# Low_Power_Brushed_Motor_Controller.net
KiCad netlist of a schematic drawn in Altium Designer
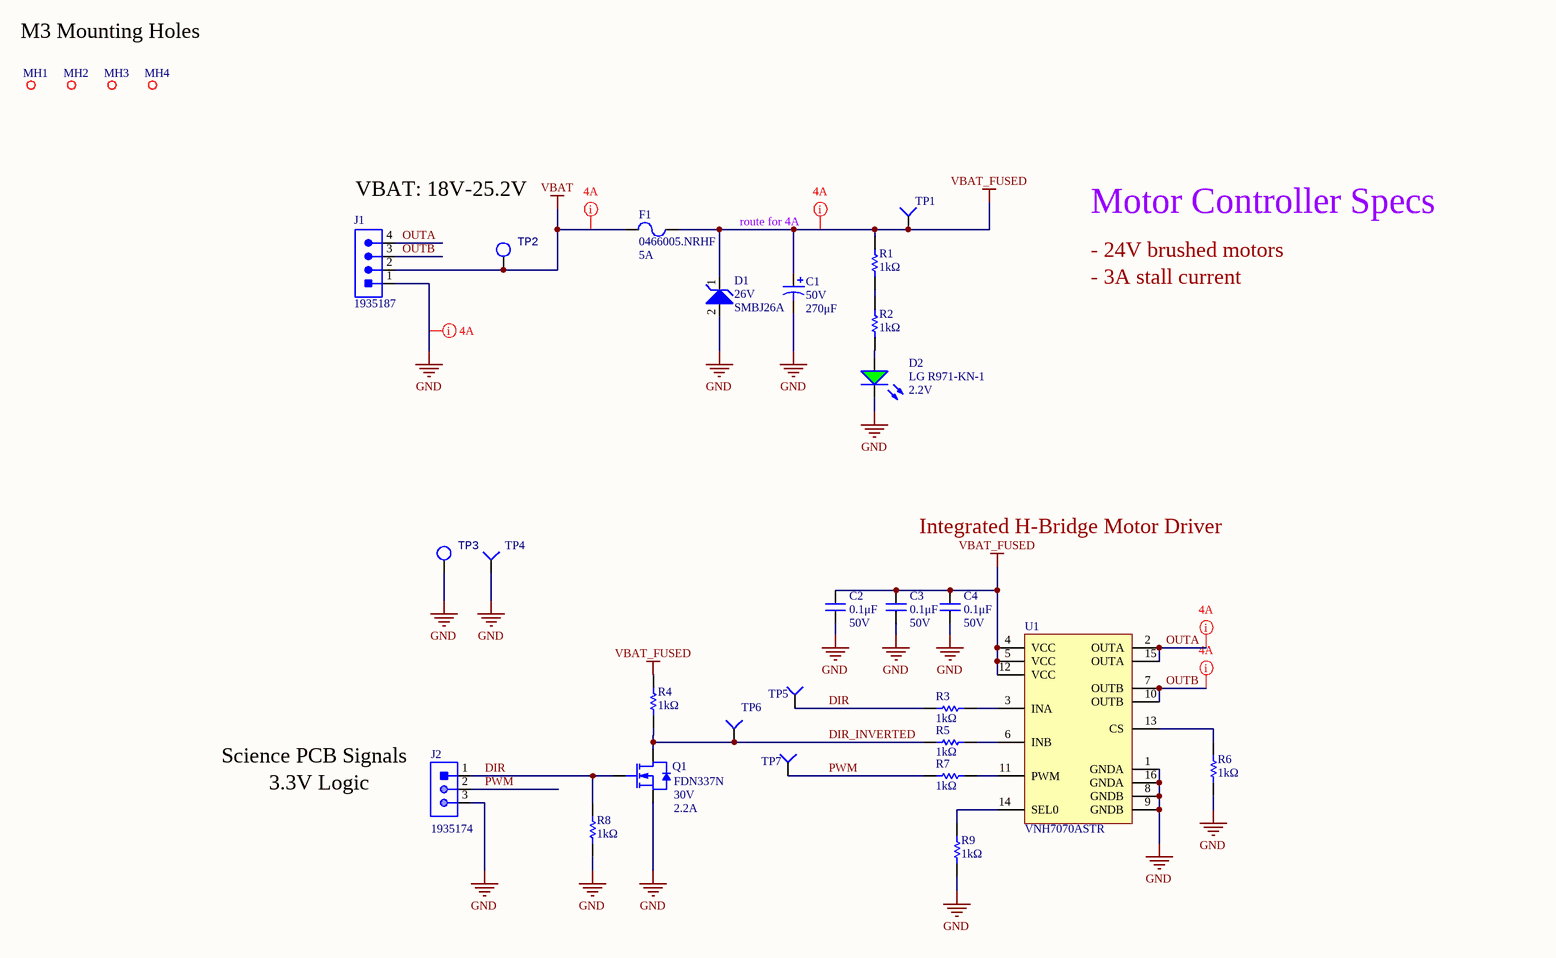
[diagram p0: Low Power Brushed Motor Controller.SchDoc]

(export (version "E")
  (design (tool "Eeschema 10.0.6"))
  (components
    (comp (ref "C1")
      (value "270μF")
      (footprint "RADIAL_PANASONIC_G")
      (description "CAP ALUM 270uF 50VDC 20% SMD")
      (fields (field (name "VOLTAGE RATING") "50V") (field (name "Comment") "CAP_270uF_50V_ALUM"))
      (libsource (lib "UWRT_Schematic_Library_2020") (part "CAP_270uF_50V_ALUM"))
    )
    (comp (ref "C2")
      (value "0.1μF")
      (footprint "CAP0603")
      (description "CAP CER 0.1UF 50V X7R 0603")
      (fields (field (name "VOLTAGE RATING") "50V") (field (name "Comment") "CAP_0.1uF_50V_0603"))
      (libsource (lib "UWRT_Schematic_Library_2020") (part "CAP_0.1uF_50V_0603"))
    )
    (comp (ref "C3")
      (value "0.1μF")
      (footprint "CAP0603")
      (description "CAP CER 0.1UF 50V X7R 0603")
      (fields (field (name "VOLTAGE RATING") "50V") (field (name "Comment") "CAP_0.1uF_50V_0603"))
      (libsource (lib "UWRT_Schematic_Library_2020") (part "CAP_0.1uF_50V_0603"))
    )
    (comp (ref "C4")
      (value "0.1μF")
      (footprint "CAP0603")
      (description "CAP CER 0.1UF 50V X7R 0603")
      (fields (field (name "VOLTAGE RATING") "50V") (field (name "Comment") "CAP_0.1uF_50V_0603"))
      (libsource (lib "UWRT_Schematic_Library_2020") (part "CAP_0.1uF_50V_0603"))
    )
    (comp (ref "D1")
      (value "TVS_DIODE_UNIDIR_26V")
      (footprint "TVS_DIODE_UNIDIRECTIONAL_SMB")
      (description "TVS DIODE 26V 42.1V DO214AA")
      (fields
        (field (name "REVERSE STANDOFF VOLTAGE") "26V")
        (field (name "MANUFACTURER PART NUMBER 1") "SMBJ26A")
      )
      (libsource (lib "UWRT_Schematic_Library_2020") (part "TVS_DIODE_UNIDIR_26V"))
    )
    (comp (ref "D2")
      (value "DIO_LED_G")
      (footprint "LED_0805_GREEN")
      (description "LED GREEN DIFFUSED 0805 SMD")
      (fields
        (field (name "FORWARD VOLTAGE DROP") "2.2V")
        (field (name "MANUFACTURER PART NUMBER 1") "LG R971-KN-1")
      )
      (libsource (lib "UWRT_Schematic_Library_2020") (part "DIO_LED_G"))
    )
    (comp (ref "F1")
      (value "FUSE_5A_1206")
      (footprint "FUSE_1206")
      (description "FUSE BOARD MNT 5A 32VAC/VDC 1206")
      (fields (field (name "MANUFACTURER PART NUMBER 1") "0466005.NRHF") (field (name "CURRENT RATING") "5A"))
      (libsource (lib "UWRT_Schematic_Library_2020") (part "FUSE_5A_1206"))
    )
    (comp (ref "J1")
      (value "CON_4M_TERM")
      (footprint "1935187")
      (description "TERM BLK 4POS SIDE ENTRY 5MM PCB")
      (fields (field (name "MANUFACTURER PART NUMBER 1") "1935187") (field (name "VOLTAGE") "300V"))
      (libsource (lib "UWRT_Schematic_Library_2020") (part "CON_4M_TERM"))
    )
    (comp (ref "J2")
      (value "CON_3M_TERM")
      (footprint "1935174")
      (description "TERM BLK 3POS SIDE ENTRY 5MM")
      (fields (field (name "MANUFACTURER PART NUMBER 1") "1935174") (field (name "VOLTAGE") "300V"))
      (libsource (lib "UWRT_Schematic_Library_2020") (part "CON_3M_TERM"))
    )
    (comp (ref "MH1")
      (value "MOUNTING_HOLE_M3")
      (footprint "MOUNTING_HOLE_3mm")
      (libsource (lib "UWRT_Schematic_Library_2020") (part "MOUNTING_HOLE_M3"))
    )
    (comp (ref "MH2")
      (value "MOUNTING_HOLE_M3")
      (footprint "MOUNTING_HOLE_3mm")
      (libsource (lib "UWRT_Schematic_Library_2020") (part "MOUNTING_HOLE_M3"))
    )
    (comp (ref "MH3")
      (value "MOUNTING_HOLE_M3")
      (footprint "MOUNTING_HOLE_3mm")
      (libsource (lib "UWRT_Schematic_Library_2020") (part "MOUNTING_HOLE_M3"))
    )
    (comp (ref "MH4")
      (value "MOUNTING_HOLE_M3")
      (footprint "MOUNTING_HOLE_3mm")
      (libsource (lib "UWRT_Schematic_Library_2020") (part "MOUNTING_HOLE_M3"))
    )
    (comp (ref "Q1")
      (value "NMOS_30V_2.2A")
      (footprint "NMOS_SSOT-3")
      (description "MOSFET N-CH 30V 2.2A SUPERSOT3")
      (fields
        (field (name "CONTINUOUS DRAIN CURRENT (ID)") "2.2A")
        (field (name "DRAIN TO SOURCE VOLTAGE (VDSS)") "30V")
        (field (name "MANUFACTURER PART NUMBER 1") "FDN337N")
      )
      (libsource (lib "UWRT_Schematic_Library_2020") (part "NMOS_30V_2.2A"))
    )
    (comp (ref "R1")
      (value "1kΩ")
      (footprint "RESC0603")
      (description "RES 1K OHM 5% 1/10W 0603")
      (fields (field (name "TOLERANCE") "5%") (field (name "Comment") "RES_1kΩ_0603_5%"))
      (libsource (lib "UWRT_Schematic_Library_2020") (part "RES_1kΩ_0603_5%"))
    )
    (comp (ref "R2")
      (value "1kΩ")
      (footprint "RESC0603")
      (description "RES 1K OHM 5% 1/10W 0603")
      (fields (field (name "TOLERANCE") "5%") (field (name "Comment") "RES_1kΩ_0603_5%"))
      (libsource (lib "UWRT_Schematic_Library_2020") (part "RES_1kΩ_0603_5%"))
    )
    (comp (ref "R3")
      (value "1kΩ")
      (footprint "RESC0603")
      (description "RES 1K OHM 5% 1/10W 0603")
      (fields (field (name "TOLERANCE") "5%") (field (name "Comment") "RES_1kΩ_0603_5%"))
      (libsource (lib "UWRT_Schematic_Library_2020") (part "RES_1kΩ_0603_5%"))
    )
    (comp (ref "R4")
      (value "1kΩ")
      (footprint "RESC0603")
      (description "RES 1K OHM 5% 1/10W 0603")
      (fields (field (name "TOLERANCE") "5%") (field (name "Comment") "RES_1kΩ_0603_5%"))
      (libsource (lib "UWRT_Schematic_Library_2020") (part "RES_1kΩ_0603_5%"))
    )
    (comp (ref "R5")
      (value "1kΩ")
      (footprint "RESC0603")
      (description "RES 1K OHM 5% 1/10W 0603")
      (fields (field (name "TOLERANCE") "5%") (field (name "Comment") "RES_1kΩ_0603_5%"))
      (libsource (lib "UWRT_Schematic_Library_2020") (part "RES_1kΩ_0603_5%"))
    )
    (comp (ref "R6")
      (value "1kΩ")
      (footprint "RESC0603")
      (description "RES 1K OHM 5% 1/10W 0603")
      (fields (field (name "TOLERANCE") "5%") (field (name "Comment") "RES_1kΩ_0603_5%"))
      (libsource (lib "UWRT_Schematic_Library_2020") (part "RES_1kΩ_0603_5%"))
    )
    (comp (ref "R7")
      (value "1kΩ")
      (footprint "RESC0603")
      (description "RES 1K OHM 5% 1/10W 0603")
      (fields (field (name "TOLERANCE") "5%") (field (name "Comment") "RES_1kΩ_0603_5%"))
      (libsource (lib "UWRT_Schematic_Library_2020") (part "RES_1kΩ_0603_5%"))
    )
    (comp (ref "R8")
      (value "1kΩ")
      (footprint "RESC0603")
      (description "RES 1K OHM 5% 1/10W 0603")
      (fields (field (name "TOLERANCE") "5%") (field (name "Comment") "RES_1kΩ_0603_5%"))
      (libsource (lib "UWRT_Schematic_Library_2020") (part "RES_1kΩ_0603_5%"))
    )
    (comp (ref "R9")
      (value "1kΩ")
      (footprint "RESC0603")
      (description "RES 1K OHM 5% 1/10W 0603")
      (fields (field (name "TOLERANCE") "5%") (field (name "Comment") "RES_1kΩ_0603_5%"))
      (libsource (lib "UWRT_Schematic_Library_2020") (part "RES_1kΩ_0603_5%"))
    )
    (comp (ref "TP1")
      (value "TESTPOINT_1MM_CIRCLE")
      (footprint "TESTPOINT_CIRCLE_1MM")
      (description "TESTPOINT 1MM CIRCLE")
      (libsource (lib "UWRT_Schematic_Library_2020") (part "TESTPOINT_1MM_CIRCLE"))
    )
    (comp (ref "TP2")
      (value "TESTPOINT_LOOP")
      (footprint "TESTPOINT_LOOP")
      (description "PC TEST POINT MINIATURE WHITE")
      (libsource (lib "UWRT_Schematic_Library_2020") (part "TESTPOINT_LOOP"))
    )
    (comp (ref "TP3")
      (value "TESTPOINT_LOOP")
      (footprint "TESTPOINT_LOOP")
      (description "PC TEST POINT MINIATURE WHITE")
      (libsource (lib "UWRT_Schematic_Library_2020") (part "TESTPOINT_LOOP"))
    )
    (comp (ref "TP4")
      (value "TESTPOINT_1MM_SQUARE")
      (footprint "TESTPOINT_SQUARE_1MM")
      (description "TESTPOINT 1MM SQUARE")
      (libsource (lib "UWRT_Schematic_Library_2020") (part "TESTPOINT_1MM_SQUARE"))
    )
    (comp (ref "TP5")
      (value "TESTPOINT_1MM_CIRCLE")
      (footprint "TESTPOINT_CIRCLE_1MM")
      (description "TESTPOINT 1MM CIRCLE")
      (libsource (lib "UWRT_Schematic_Library_2020") (part "TESTPOINT_1MM_CIRCLE"))
    )
    (comp (ref "TP6")
      (value "TESTPOINT_1MM_CIRCLE")
      (footprint "TESTPOINT_CIRCLE_1MM")
      (description "TESTPOINT 1MM CIRCLE")
      (libsource (lib "UWRT_Schematic_Library_2020") (part "TESTPOINT_1MM_CIRCLE"))
    )
    (comp (ref "TP7")
      (value "TESTPOINT_1MM_CIRCLE")
      (footprint "TESTPOINT_CIRCLE_1MM")
      (description "TESTPOINT 1MM CIRCLE")
      (libsource (lib "UWRT_Schematic_Library_2020") (part "TESTPOINT_1MM_CIRCLE"))
    )
    (comp (ref "U1")
      (value "IC_MOTOR_DRIVER_ST")
      (footprint "SO-16N")
      (description "IC MOTOR DRIVER 4V-28V 16SOIC")
      (fields (field (name "MANUFACTURER PART NUMBER 1") "VNH7070ASTR"))
      (libsource (lib "UWRT_Schematic_Library_2020") (part "IC_MOTOR_DRIVER_ST"))
    )
  )
  (nets
    (net (code "1") (name "/DIR") (class "Default")
      (node (ref "J2") (pin "1") (pinfunction "1_1") (pintype "passive"))
      (node (ref "Q1") (pin "1") (pinfunction "GATE_1") (pintype "passive"))
      (node (ref "R3") (pin "1") (pinfunction "1_1") (pintype "passive"))
      (node (ref "R8") (pin "2") (pinfunction "2_2") (pintype "passive"))
      (node (ref "TP5") (pin "1") (pinfunction "=value_1") (pintype "passive"))
    )
    (net (code "2") (name "/DIR_INVERTED") (class "Default")
      (node (ref "Q1") (pin "3") (pinfunction "DRAIN_3") (pintype "passive"))
      (node (ref "R4") (pin "1") (pinfunction "1_1") (pintype "passive"))
      (node (ref "R5") (pin "1") (pinfunction "1_1") (pintype "passive"))
      (node (ref "TP6") (pin "1") (pinfunction "=value_1") (pintype "passive"))
    )
    (net (code "3") (name "/OUTA") (class "Default")
      (node (ref "J1") (pin "4") (pinfunction "4_4") (pintype "passive"))
      (node (ref "U1") (pin "15") (pinfunction "OUTA_15") (pintype "passive"))
      (node (ref "U1") (pin "2") (pinfunction "OUTA_2") (pintype "passive"))
    )
    (net (code "4") (name "/OUTB") (class "Default")
      (node (ref "J1") (pin "3") (pinfunction "3_3") (pintype "passive"))
      (node (ref "U1") (pin "10") (pinfunction "OUTB_10") (pintype "passive"))
      (node (ref "U1") (pin "7") (pinfunction "OUTB_7") (pintype "passive"))
    )
    (net (code "5") (name "/PWM") (class "Default")
      (node (ref "J2") (pin "2") (pinfunction "2_2") (pintype "passive"))
      (node (ref "R7") (pin "1") (pinfunction "1_1") (pintype "passive"))
      (node (ref "TP7") (pin "1") (pinfunction "=value_1") (pintype "passive"))
    )
    (net (code "6") (name "GND") (class "Default")
      (node (ref "C1") (pin "2") (pinfunction "2_2") (pintype "passive"))
      (node (ref "C2") (pin "1") (pinfunction "1_1") (pintype "passive"))
      (node (ref "C3") (pin "1") (pinfunction "1_1") (pintype "passive"))
      (node (ref "C4") (pin "2") (pinfunction "2_2") (pintype "passive"))
      (node (ref "D1") (pin "2") (pinfunction "Anode_2") (pintype "passive"))
      (node (ref "D2") (pin "2") (pinfunction "K_2") (pintype "passive"))
      (node (ref "J1") (pin "1") (pinfunction "1_1") (pintype "passive"))
      (node (ref "J2") (pin "3") (pinfunction "3_3") (pintype "passive"))
      (node (ref "Q1") (pin "2") (pinfunction "SOURCE_2") (pintype "passive"))
      (node (ref "R6") (pin "1") (pinfunction "1_1") (pintype "passive"))
      (node (ref "R8") (pin "1") (pinfunction "1_1") (pintype "passive"))
      (node (ref "R9") (pin "1") (pinfunction "1_1") (pintype "passive"))
      (node (ref "TP3") (pin "1") (pintype "passive"))
      (node (ref "TP4") (pin "1") (pinfunction "=value_1") (pintype "passive"))
      (node (ref "U1") (pin "1") (pinfunction "GNDA_1") (pintype "power_in"))
      (node (ref "U1") (pin "16") (pinfunction "GNDA_16") (pintype "power_in"))
      (node (ref "U1") (pin "8") (pinfunction "GNDB_8") (pintype "power_in"))
      (node (ref "U1") (pin "9") (pinfunction "GNDB_9") (pintype "power_in"))
    )
    (net (code "7") (name "Net-(D2-A)") (class "Default")
      (node (ref "D2") (pin "1") (pinfunction "A_1") (pintype "passive"))
      (node (ref "R2") (pin "1") (pinfunction "1_1") (pintype "passive"))
    )
    (net (code "8") (name "Net-(R1-Pad1)") (class "Default")
      (node (ref "R1") (pin "1") (pinfunction "1_1") (pintype "passive"))
      (node (ref "R2") (pin "2") (pinfunction "2_2") (pintype "passive"))
    )
    (net (code "9") (name "Net-(U1-CS)") (class "Default")
      (node (ref "R6") (pin "2") (pinfunction "2_2") (pintype "passive"))
      (node (ref "U1") (pin "13") (pinfunction "CS_13") (pintype "passive"))
    )
    (net (code "10") (name "Net-(U1-INA)") (class "Default")
      (node (ref "R3") (pin "2") (pinfunction "2_2") (pintype "passive"))
      (node (ref "U1") (pin "3") (pinfunction "INA_3") (pintype "passive"))
    )
    (net (code "11") (name "Net-(U1-INB)") (class "Default")
      (node (ref "R5") (pin "2") (pinfunction "2_2") (pintype "passive"))
      (node (ref "U1") (pin "6") (pinfunction "INB_6") (pintype "passive"))
    )
    (net (code "12") (name "Net-(U1-PWM)") (class "Default")
      (node (ref "R7") (pin "2") (pinfunction "2_2") (pintype "passive"))
      (node (ref "U1") (pin "11") (pinfunction "PWM_11") (pintype "passive"))
    )
    (net (code "13") (name "Net-(U1-SEL0)") (class "Default")
      (node (ref "R9") (pin "2") (pinfunction "2_2") (pintype "passive"))
      (node (ref "U1") (pin "14") (pinfunction "SEL0_14") (pintype "passive"))
    )
    (net (code "14") (name "VBAT") (class "Default")
      (node (ref "F1") (pin "1") (pinfunction "1_1") (pintype "passive"))
      (node (ref "J1") (pin "2") (pinfunction "2_2") (pintype "passive"))
      (node (ref "TP2") (pin "1") (pintype "passive"))
    )
    (net (code "15") (name "VBAT_FUSED") (class "Default")
      (node (ref "C1") (pin "1") (pinfunction "1_1") (pintype "passive"))
      (node (ref "C2") (pin "2") (pinfunction "2_2") (pintype "passive"))
      (node (ref "C3") (pin "2") (pinfunction "2_2") (pintype "passive"))
      (node (ref "C4") (pin "1") (pinfunction "1_1") (pintype "passive"))
      (node (ref "D1") (pin "1") (pinfunction "Cathode_1") (pintype "passive"))
      (node (ref "F1") (pin "2") (pinfunction "2_2") (pintype "passive"))
      (node (ref "R1") (pin "2") (pinfunction "2_2") (pintype "passive"))
      (node (ref "R4") (pin "2") (pinfunction "2_2") (pintype "passive"))
      (node (ref "TP1") (pin "1") (pinfunction "=value_1") (pintype "passive"))
      (node (ref "U1") (pin "12") (pinfunction "VCC_12") (pintype "power_in"))
      (node (ref "U1") (pin "4") (pinfunction "VCC_4") (pintype "power_in"))
      (node (ref "U1") (pin "5") (pinfunction "VCC_5") (pintype "power_in"))
    )
  )
)
